# RobotPatient_BMI270.net
KiCad netlist of a schematic drawn in EAGLE
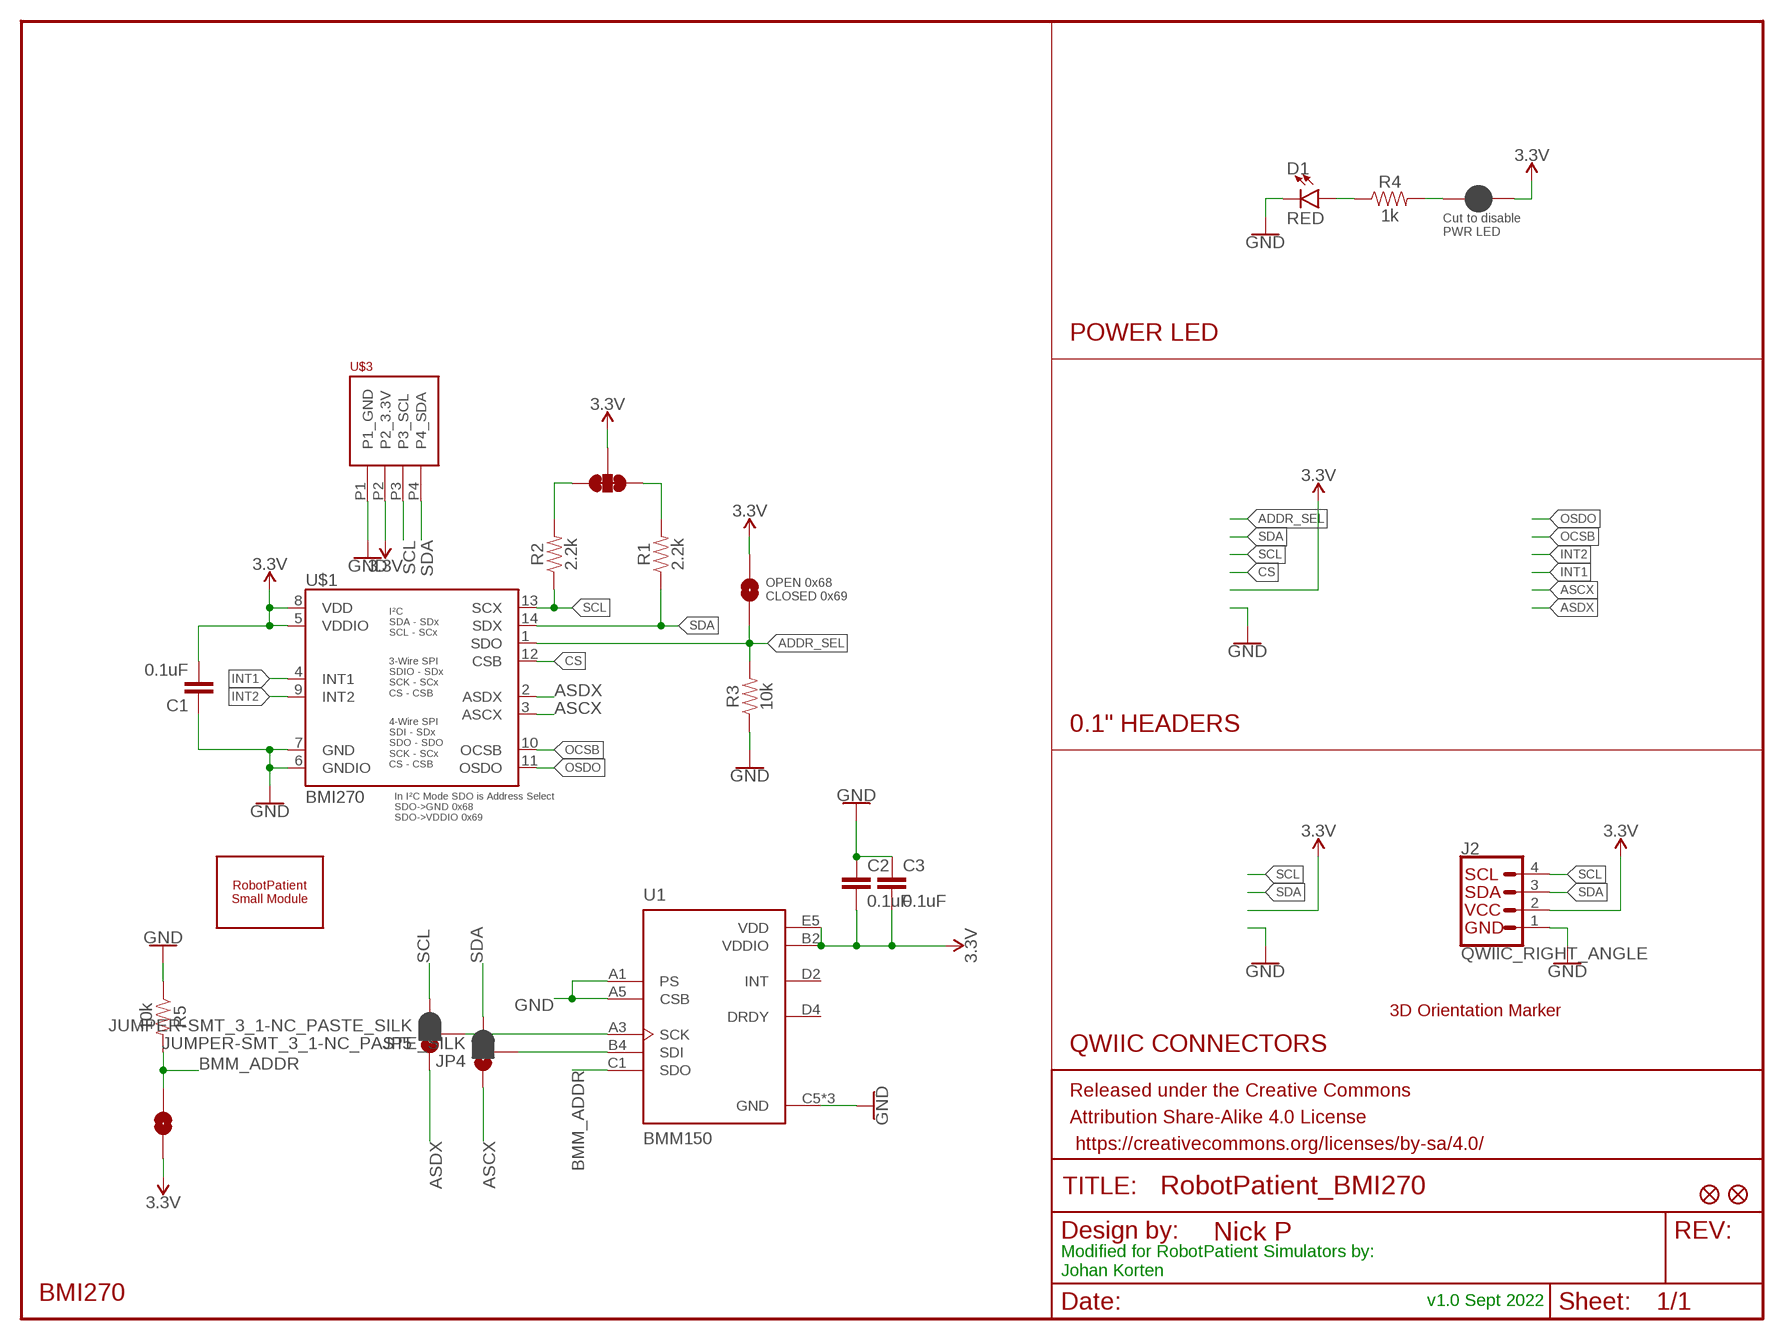
[diagram p0: schematic, sheet 1]

(export (version "E")
  (design (tool "Eeschema 10.0.6"))
  (components
    (comp (ref "C1")
      (value "0.1uF")
      (footprint "eagle-import:0603")
      (libsource (lib "eagle-import") (part "0.1UF-0603-25V-(+80/-20%)"))
    )
    (comp (ref "C2")
      (value "0.1uF")
      (footprint "eagle-import:0603")
      (libsource (lib "eagle-import") (part "SparkFun-Capacitors_510_0.1UF-0603-25V-(+80/-20%)"))
    )
    (comp (ref "C3")
      (value "0.1uF")
      (footprint "eagle-import:0603")
      (libsource (lib "eagle-import") (part "SparkFun-Capacitors_510_0.1UF-0603-25V-(+80/-20%)"))
    )
    (comp (ref "D1")
      (value "RED")
      (footprint "eagle-import:LED-0603")
      (libsource (lib "eagle-import") (part "LED-RED0603"))
    )
    (comp (ref "FD1")
      (value "FIDUCIAL1X2")
      (footprint "eagle-import:FIDUCIAL-1X2")
      (libsource (lib "eagle-import") (part "FIDUCIAL1X2"))
    )
    (comp (ref "FD2")
      (value "FIDUCIAL1X2")
      (footprint "eagle-import:FIDUCIAL-1X2")
      (libsource (lib "eagle-import") (part "FIDUCIAL1X2"))
    )
    (comp (ref "FRAME1")
      (value "FRAME-LETTERNO_PACKAGE")
      (footprint "eagle-import:DUMMY")
      (fields
        (field (name "DESIGNER") "Nobody")
        (field (name "DESIGNER_1") "Nick P")
        (field (name "VERSION") "1.0 Sep 22")
      )
      (libsource (lib "eagle-import") (part "FRAME-LETTERNO_PACKAGE"))
    )
    (comp (ref "J2")
      (value "QWIIC_RIGHT_ANGLE")
      (footprint "eagle-import:JST04_1MM_RA")
      (libsource (lib "eagle-import") (part "QWIIC_CONNECTORJS-1MM"))
    )
    (comp (ref "JP1")
      (value "JUMPER-SMT_3_2-NC_TRACE_SILK")
      (footprint "eagle-import:SMT-JUMPER_3_2-NC_TRACE_SILK")
      (libsource (lib "eagle-import") (part "JUMPER-SMT_3_2-NC_TRACE_SILK"))
    )
    (comp (ref "JP2")
      (value "JUMPER-SMT_2_NO_SILK")
      (footprint "eagle-import:SMT-JUMPER_2_NO_SILK")
      (libsource (lib "eagle-import") (part "JUMPER-SMT_2_NO_SILK"))
    )
    (comp (ref "JP3")
      (value "JUMPER-SMT_2_NC_PASTE_SILK")
      (footprint "eagle-import:SMT-JUMPER_2_NC_PASTE_SILK")
      (libsource (lib "eagle-import") (part "JUMPER-SMT_2_NC_PASTE_SILK"))
    )
    (comp (ref "JP4")
      (value "JUMPER-SMT_3_1-NC_PASTE_SILK")
      (footprint "eagle-import:SMT-JUMPER_3_1-NC_PASTE_SILK")
      (libsource (lib "eagle-import") (part "JUMPER-SMT_3_1-NC_PASTE_SILK"))
    )
    (comp (ref "JP5")
      (value "JUMPER-SMT_3_1-NC_PASTE_SILK")
      (footprint "eagle-import:SMT-JUMPER_3_1-NC_PASTE_SILK")
      (libsource (lib "eagle-import") (part "JUMPER-SMT_3_1-NC_PASTE_SILK"))
    )
    (comp (ref "JP6")
      (value "JUMPER-SMT_2_NO_SILK")
      (footprint "eagle-import:SMT-JUMPER_2_NO_SILK")
      (libsource (lib "eagle-import") (part "JUMPER-SMT_2_NO_SILK"))
    )
    (comp (ref "R1")
      (value "2.2k")
      (footprint "eagle-import:0603")
      (libsource (lib "eagle-import") (part "2.2KOHM-0603-1/10W-1%"))
    )
    (comp (ref "R2")
      (value "2.2k")
      (footprint "eagle-import:0603")
      (libsource (lib "eagle-import") (part "2.2KOHM-0603-1/10W-1%"))
    )
    (comp (ref "R3")
      (value "10k")
      (footprint "eagle-import:0603")
      (libsource (lib "eagle-import") (part "10KOHM-0603-1/10W-1%"))
    )
    (comp (ref "R4")
      (value "1k")
      (footprint "eagle-import:0603")
      (libsource (lib "eagle-import") (part "1KOHM-0603-1/10W-1%"))
    )
    (comp (ref "R5")
      (value "10k")
      (footprint "eagle-import:0603")
      (libsource (lib "eagle-import") (part "10KOHM-0603-1/10W-1%"))
    )
    (comp (ref "U$1")
      (value "BMI270")
      (footprint "eagle-import:BMI270")
      (libsource (lib "eagle-import") (part "BMI270"))
    )
    (comp (ref "U$2")
      (value "3D_MARKER")
      (footprint "eagle-import:3D_MARKER")
      (libsource (lib "eagle-import") (part "3D_MARKER"))
    )
    (comp (ref "U$3")
      (value "PHOENIX_PTSM_M4_THANGLE")
      (footprint "eagle-import:PTSM_M4_TH")
      (libsource (lib "eagle-import") (part "PHOENIX_PTSM_M4_THANGLE"))
    )
    (comp (ref "U$40")
      (value "ROBOTPATIENT_SMALL_MODULEBOARD")
      (footprint "eagle-import:RP_SMALL_SENSOR_OUTLINE")
      (libsource (lib "eagle-import") (part "ROBOTPATIENT_SMALL_MODULEBOARD"))
    )
    (comp (ref "U1")
      (value "BMM150")
      (footprint "eagle-import:XDCR_BMM150")
      (fields (field (name "MF") "Bosch Sensortec"))
      (libsource (lib "eagle-import") (part "BMM150"))
    )
  )
  (nets
    (net (code "1") (name "/BMM_ADDR") (class "Default")
      (node (ref "JP6") (pin "1") (pinfunction "1_1") (pintype "passive"))
      (node (ref "R5") (pin "2") (pinfunction "2_2") (pintype "passive"))
      (node (ref "U1") (pin "C1") (pinfunction "SDO_C1") (pintype "output"))
    )
    (net (code "2") (name "3.3V") (class "Default")
      (node (ref "C1") (pin "2") (pinfunction "2_2") (pintype "passive"))
      (node (ref "C2") (pin "2") (pinfunction "2_2") (pintype "passive"))
      (node (ref "C3") (pin "2") (pinfunction "2_2") (pintype "passive"))
      (node (ref "J2") (pin "2") (pinfunction "2_2") (pintype "power_in"))
      (node (ref "JP1") (pin "2") (pinfunction "2_2") (pintype "passive"))
      (node (ref "JP2") (pin "2") (pinfunction "2_2") (pintype "passive"))
      (node (ref "JP3") (pin "2") (pinfunction "2_2") (pintype "passive"))
      (node (ref "JP6") (pin "2") (pinfunction "2_2") (pintype "passive"))
      (node (ref "U$1") (pin "5") (pinfunction "VDDIO_5") (pintype "bidirectional"))
      (node (ref "U$1") (pin "8") (pinfunction "VDD_8") (pintype "bidirectional"))
      (node (ref "U$3") (pin "P2") (pinfunction "P2_3.3V_P2") (pintype "power_in"))
      (node (ref "U1") (pin "B2") (pinfunction "VDDIO_B2") (pintype "power_in"))
      (node (ref "U1") (pin "E5") (pinfunction "VDD_E5") (pintype "power_in"))
    )
    (net (code "3") (name "ADDR_SEL") (class "Default")
      (node (ref "JP2") (pin "1") (pinfunction "1_1") (pintype "passive"))
      (node (ref "R3") (pin "2") (pinfunction "2_2") (pintype "passive"))
      (node (ref "U$1") (pin "1") (pinfunction "SDO_1") (pintype "bidirectional"))
    )
    (net (code "4") (name "ASCX") (class "Default")
      (node (ref "JP4") (pin "1") (pinfunction "1_1") (pintype "passive"))
      (node (ref "U$1") (pin "3") (pinfunction "ASCX_3") (pintype "bidirectional"))
    )
    (net (code "5") (name "ASDX") (class "Default")
      (node (ref "JP5") (pin "1") (pinfunction "1_1") (pintype "passive"))
      (node (ref "U$1") (pin "2") (pinfunction "ASDX_2") (pintype "bidirectional"))
    )
    (net (code "6") (name "CS") (class "Default")
      (node (ref "U$1") (pin "12") (pinfunction "CSB_12") (pintype "bidirectional"))
    )
    (net (code "7") (name "GND") (class "Default")
      (node (ref "C1") (pin "1") (pinfunction "1_1") (pintype "passive"))
      (node (ref "C2") (pin "1") (pinfunction "1_1") (pintype "passive"))
      (node (ref "C3") (pin "1") (pinfunction "1_1") (pintype "passive"))
      (node (ref "D1") (pin "C") (pinfunction "C_C") (pintype "passive"))
      (node (ref "J2") (pin "1") (pinfunction "1_1") (pintype "power_in"))
      (node (ref "R3") (pin "1") (pinfunction "1_1") (pintype "passive"))
      (node (ref "R5") (pin "1") (pinfunction "1_1") (pintype "passive"))
      (node (ref "U$1") (pin "6") (pinfunction "GNDIO_6") (pintype "bidirectional"))
      (node (ref "U$1") (pin "7") (pinfunction "GND_7") (pintype "bidirectional"))
      (node (ref "U$3") (pin "P1") (pinfunction "P1_GND_P1") (pintype "power_in"))
      (node (ref "U1") (pin "A1") (pinfunction "PS_A1") (pintype "input"))
      (node (ref "U1") (pin "A5") (pinfunction "CSB_A5") (pintype "input"))
      (node (ref "U1") (pin "C5") (pinfunction "GND_C5") (pintype "power_in"))
      (node (ref "U1") (pin "E1") (pinfunction "GND_E1") (pintype "power_in"))
      (node (ref "U1") (pin "E3") (pinfunction "GND_E3") (pintype "power_in"))
    )
    (net (code "8") (name "INT1") (class "Default")
      (node (ref "U$1") (pin "4") (pinfunction "INT1_4") (pintype "bidirectional"))
    )
    (net (code "9") (name "INT2") (class "Default")
      (node (ref "U$1") (pin "9") (pinfunction "INT2_9") (pintype "bidirectional"))
    )
    (net (code "10") (name "Net-(D1-PadA)") (class "Default")
      (node (ref "D1") (pin "A") (pinfunction "A_A") (pintype "passive"))
      (node (ref "R4") (pin "1") (pinfunction "1_1") (pintype "passive"))
    )
    (net (code "11") (name "Net-(JP1-Pad1)") (class "Default")
      (node (ref "JP1") (pin "1") (pinfunction "1_1") (pintype "passive"))
      (node (ref "R1") (pin "2") (pinfunction "2_2") (pintype "passive"))
    )
    (net (code "12") (name "Net-(JP1-Pad3)") (class "Default")
      (node (ref "JP1") (pin "3") (pinfunction "3_3") (pintype "passive"))
      (node (ref "R2") (pin "2") (pinfunction "2_2") (pintype "passive"))
    )
    (net (code "13") (name "Net-(JP3-Pad1)") (class "Default")
      (node (ref "JP3") (pin "1") (pinfunction "1_1") (pintype "passive"))
      (node (ref "R4") (pin "2") (pinfunction "2_2") (pintype "passive"))
    )
    (net (code "14") (name "Net-(U1-SCK)") (class "Default")
      (node (ref "JP5") (pin "2") (pinfunction "2_2") (pintype "passive"))
      (node (ref "U1") (pin "A3") (pinfunction "SCK_A3") (pintype "input"))
    )
    (net (code "15") (name "Net-(U1-SDI)") (class "Default")
      (node (ref "JP4") (pin "2") (pinfunction "2_2") (pintype "passive"))
      (node (ref "U1") (pin "B4") (pinfunction "SDI_B4") (pintype "bidirectional"))
    )
    (net (code "16") (name "OCSB") (class "Default")
      (node (ref "U$1") (pin "10") (pinfunction "OCSB_10") (pintype "bidirectional"))
    )
    (net (code "17") (name "OSDO") (class "Default")
      (node (ref "U$1") (pin "11") (pinfunction "OSDO_11") (pintype "bidirectional"))
    )
    (net (code "18") (name "SCL") (class "Default")
      (node (ref "J2") (pin "4") (pinfunction "4_4") (pintype "passive"))
      (node (ref "JP5") (pin "3") (pinfunction "3_3") (pintype "passive"))
      (node (ref "R2") (pin "1") (pinfunction "1_1") (pintype "passive"))
      (node (ref "U$1") (pin "13") (pinfunction "SCX_13") (pintype "bidirectional"))
      (node (ref "U$3") (pin "P3") (pinfunction "P3_SCL_P3") (pintype "bidirectional"))
    )
    (net (code "19") (name "SDA") (class "Default")
      (node (ref "J2") (pin "3") (pinfunction "3_3") (pintype "passive"))
      (node (ref "JP4") (pin "3") (pinfunction "3_3") (pintype "passive"))
      (node (ref "R1") (pin "1") (pinfunction "1_1") (pintype "passive"))
      (node (ref "U$1") (pin "14") (pinfunction "SDX_14") (pintype "bidirectional"))
      (node (ref "U$3") (pin "P4") (pinfunction "P4_SDA_P4") (pintype "bidirectional"))
    )
    (net (code "20") (name "unconnected-(U1-DRDY-PadD4)") (class "Default")
      (node (ref "U1") (pin "D4") (pinfunction "DRDY_D4") (pintype "output"))
    )
    (net (code "21") (name "unconnected-(U1-INT-PadD2)") (class "Default")
      (node (ref "U1") (pin "D2") (pinfunction "INT_D2") (pintype "output"))
    )
  )
)
